# ProPrj___2025-12-10.net
KiCad netlist of a schematic drawn in EasyEDA Pro
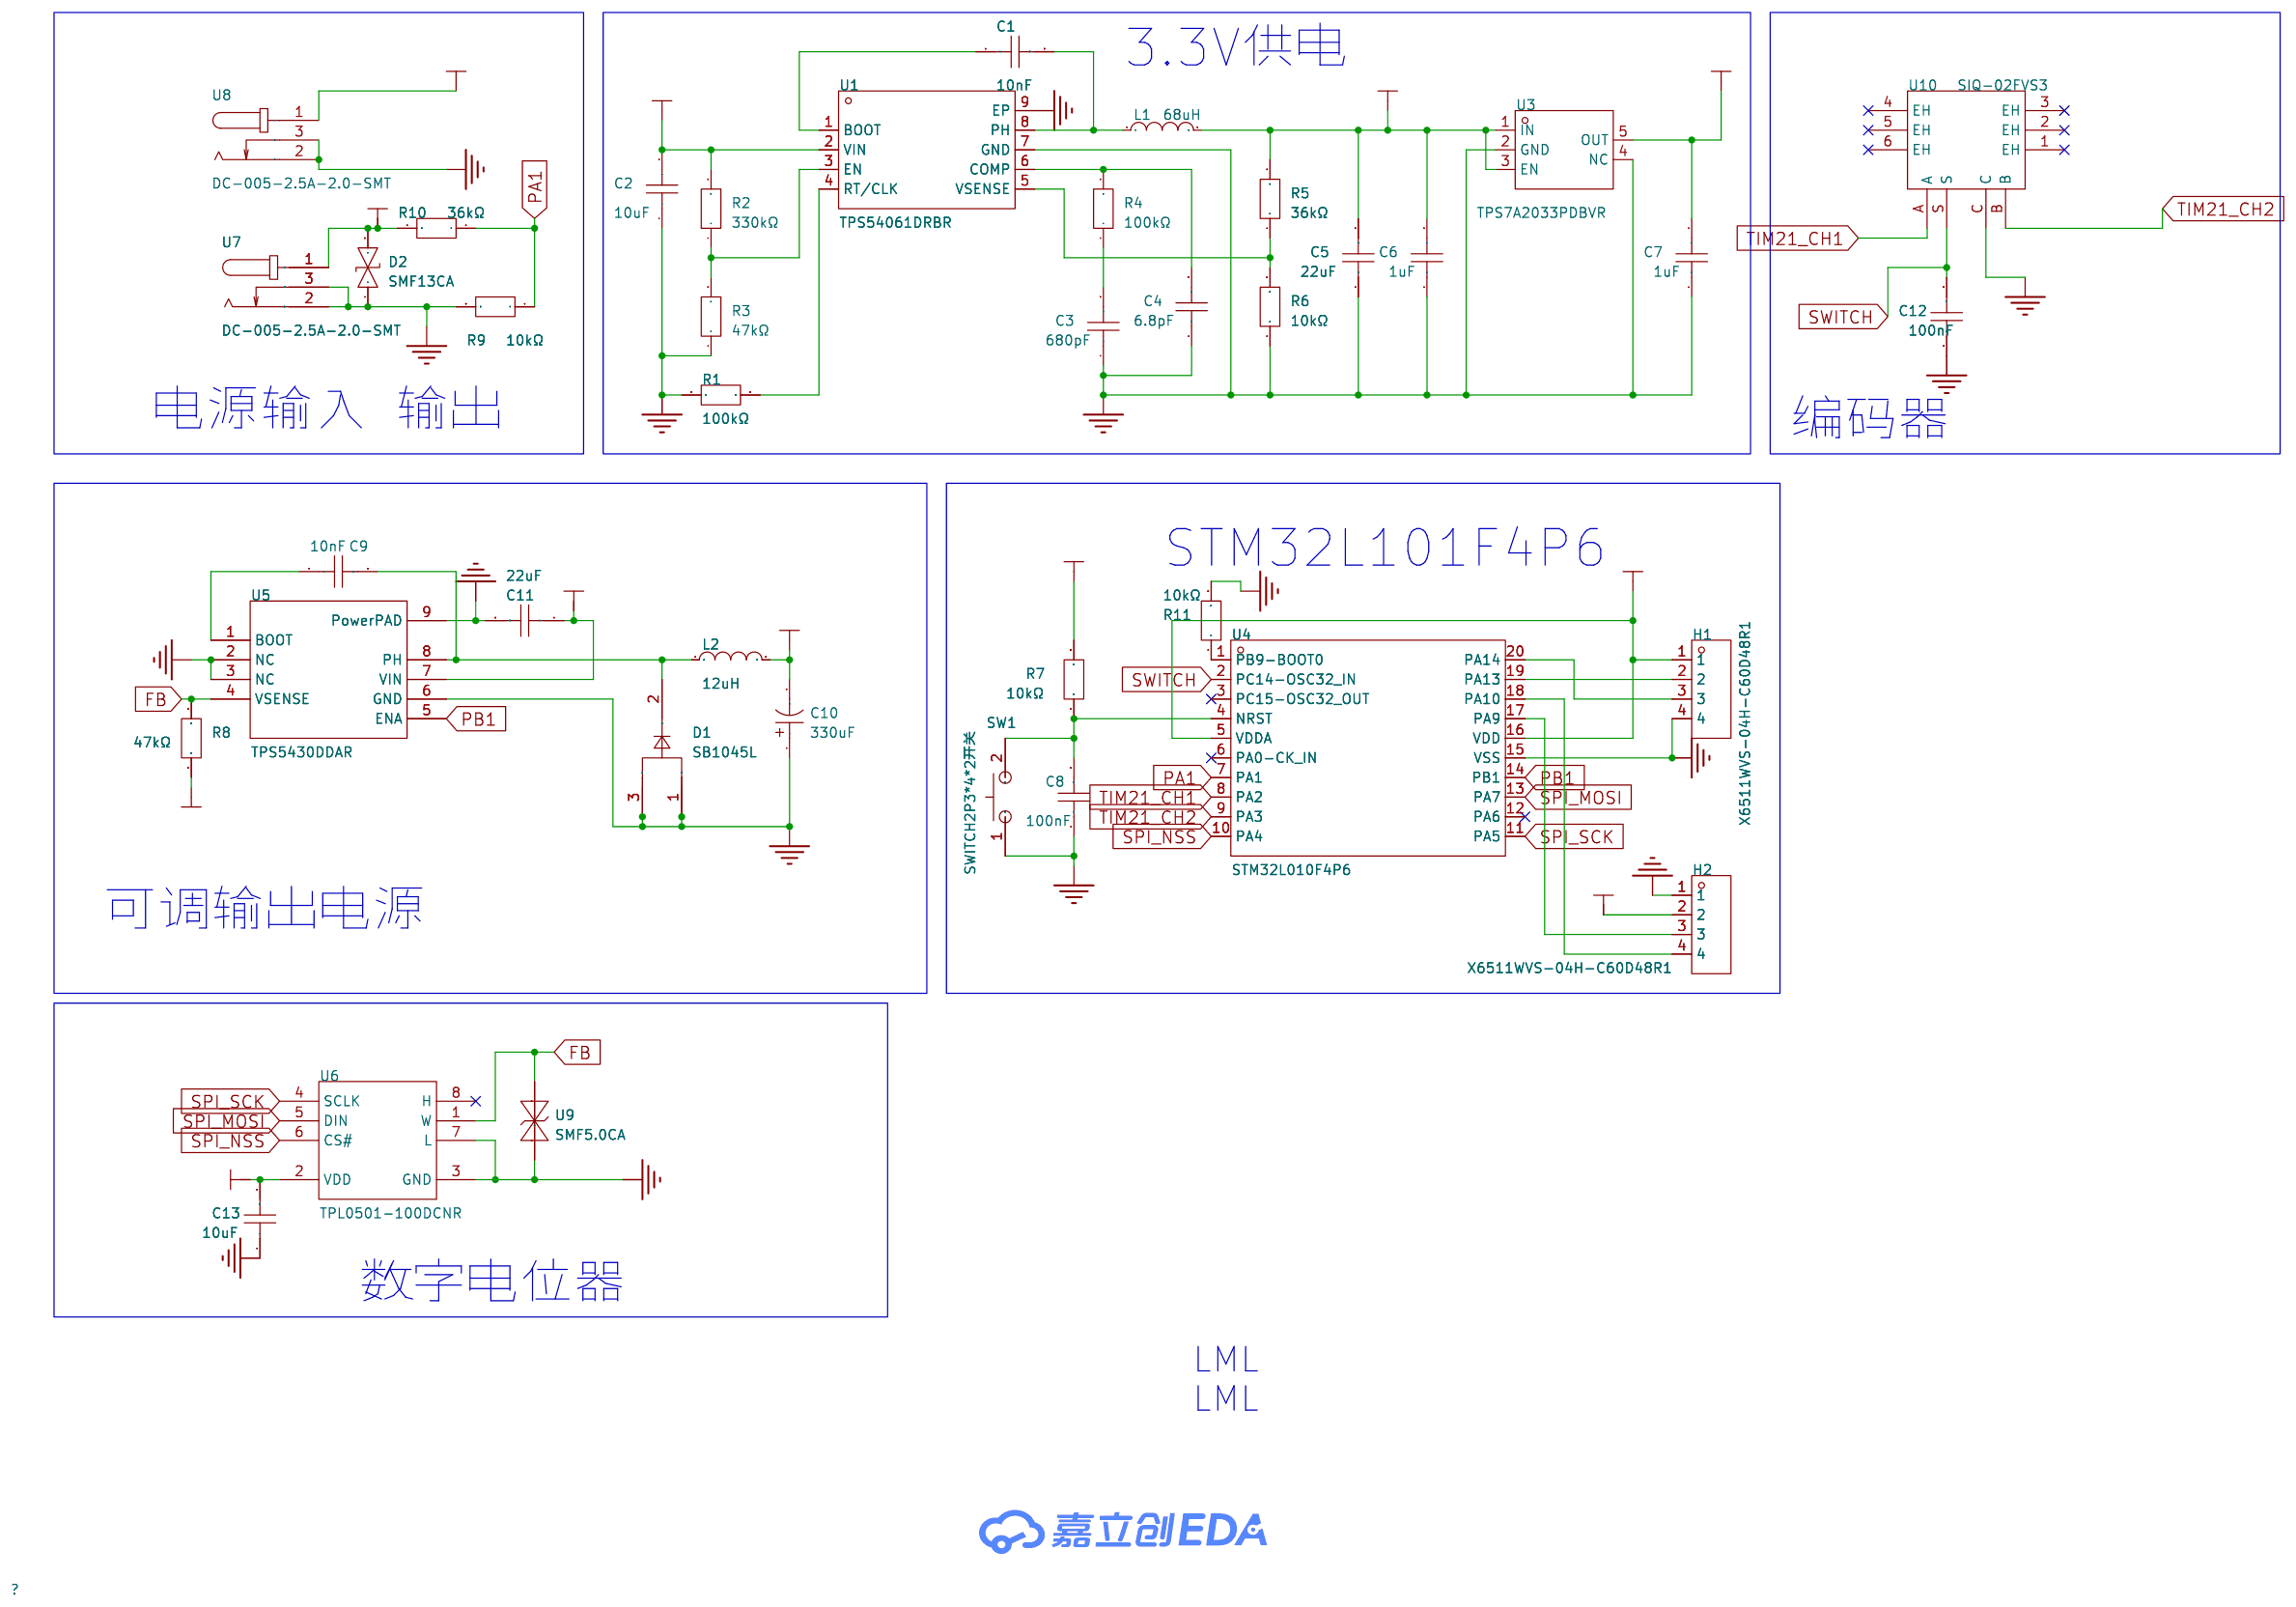
[diagram p0: schematic sheet]

(export (version "E")
  (design (tool "Eeschema 10.0.6"))
  (components
    (comp (ref "C1")
      (value "10nF")
      (footprint "easyedapro:C0603")
      (description "容值:10nF;精度:±10%;额定电压:50V;温度系数:X7R;")
      (fields
        (field (name "Manufacturer Part") "AC0603KPX7R9BB103")
        (field (name "Manufacturer") "YAGEO(国巨)")
      )
      (libsource (lib "easyedapro") (part "AC0603KPX7R9BB103"))
    )
    (comp (ref "C2")
      (value "10uF")
      (footprint "easyedapro:C0603")
      (description "容值:4.7uF;精度:±10%;额定电压:16V;温度系数:X7R;")
      (fields
        (field (name "Manufacturer Part") "GRM188Z71C475KE21J")
        (field (name "Manufacturer") "muRata(村田)")
      )
      (libsource (lib "easyedapro") (part "GRM188Z71C475KE21J"))
    )
    (comp (ref "C3")
      (value "680pF")
      (footprint "easyedapro:C0603")
      (description "容值:4.7uF;精度:±10%;额定电压:16V;温度系数:X7R;")
      (fields
        (field (name "Manufacturer Part") "GRM188Z71C475KE21J")
        (field (name "Manufacturer") "muRata(村田)")
      )
      (libsource (lib "easyedapro") (part "GRM188Z71C475KE21J"))
    )
    (comp (ref "C4")
      (value "6.8pF")
      (footprint "easyedapro:C0603")
      (description "容值:4.7uF;精度:±10%;额定电压:16V;温度系数:X7R;")
      (fields
        (field (name "Manufacturer Part") "GRM188Z71C475KE21J")
        (field (name "Manufacturer") "muRata(村田)")
      )
      (libsource (lib "easyedapro") (part "GRM188Z71C475KE21J"))
    )
    (comp (ref "C5")
      (value "22uF")
      (footprint "easyedapro:C0603")
      (description "容值:4.7uF;精度:±10%;额定电压:16V;温度系数:X7R;")
      (fields
        (field (name "Manufacturer Part") "GRM188Z71C475KE21J")
        (field (name "Manufacturer") "muRata(村田)")
      )
      (libsource (lib "easyedapro") (part "GRM188Z71C475KE21J"))
    )
    (comp (ref "C6")
      (value "1uF")
      (footprint "easyedapro:C0603")
      (description "容值:4.7uF;精度:±10%;额定电压:16V;温度系数:X7R;")
      (fields
        (field (name "Manufacturer Part") "GRM188Z71C475KE21J")
        (field (name "Manufacturer") "muRata(村田)")
      )
      (libsource (lib "easyedapro") (part "GRM188Z71C475KE21J"))
    )
    (comp (ref "C7")
      (value "1uF")
      (footprint "easyedapro:C0603")
      (description "容值:4.7uF;精度:±10%;额定电压:16V;温度系数:X7R;")
      (fields
        (field (name "Manufacturer Part") "GRM188Z71C475KE21J")
        (field (name "Manufacturer") "muRata(村田)")
      )
      (libsource (lib "easyedapro") (part "GRM188Z71C475KE21J"))
    )
    (comp (ref "C8")
      (value "100nF")
      (footprint "easyedapro:C0603")
      (description "容值:10nF;精度:±10%;额定电压:50V;温度系数:X7R;")
      (fields
        (field (name "Manufacturer Part") "AC0603KPX7R9BB103")
        (field (name "Manufacturer") "YAGEO(国巨)")
      )
      (libsource (lib "easyedapro") (part "AC0603KPX7R9BB103"))
    )
    (comp (ref "C9")
      (value "10nF")
      (footprint "easyedapro:C0603")
      (description "容值:10nF;精度:±10%;额定电压:50V;温度系数:X7R;")
      (fields
        (field (name "Manufacturer Part") "AC0603KPX7R9BB103")
        (field (name "Manufacturer") "YAGEO(国巨)")
      )
      (libsource (lib "easyedapro") (part "AC0603KPX7R9BB103"))
    )
    (comp (ref "C10")
      (value "330uF")
      (footprint "easyedapro:CAP-SMD_BD10.0-L10.3-W10.3-SV331M250G12R7R1Z00ZZ")
      (description "容值:330uF;精度:±20%;额定电压:25V;纹波电流:-;等效串联电阻(ESR):-;类型:聚合物;")
      (fields (field (name "Manufacturer Part") "SV331M250G12R7R1Z00ZZ") (field (name "Manufacturer") "创慧电子"))
      (libsource (lib "easyedapro") (part "SV331M250G12R7R1Z00ZZ"))
    )
    (comp (ref "C11")
      (value "22uF")
      (footprint "easyedapro:C0603")
      (description "容值:4.7uF;精度:±10%;额定电压:16V;温度系数:X7R;")
      (fields
        (field (name "Manufacturer Part") "GRM188Z71C475KE21J")
        (field (name "Manufacturer") "muRata(村田)")
      )
      (libsource (lib "easyedapro") (part "GRM188Z71C475KE21J"))
    )
    (comp (ref "C12")
      (value "100nF")
      (footprint "easyedapro:C0603")
      (description "容值:4.7uF;精度:±10%;额定电压:16V;温度系数:X7R;")
      (fields
        (field (name "Manufacturer Part") "GRM188Z71C475KE21J")
        (field (name "Manufacturer") "muRata(村田)")
      )
      (libsource (lib "easyedapro") (part "GRM188Z71C475KE21J"))
    )
    (comp (ref "C13")
      (value "10uF")
      (footprint "easyedapro:C0603")
      (description "容值:4.7uF;精度:±10%;额定电压:16V;温度系数:X7R;")
      (fields
        (field (name "Manufacturer Part") "GRM188Z71C475KE21J")
        (field (name "Manufacturer") "muRata(村田)")
      )
      (libsource (lib "easyedapro") (part "GRM188Z71C475KE21J"))
    )
    (comp (ref "D1")
      (value "SB1045L")
      (footprint "easyedapro:TO-277_3P-L5.4-W4.0-LS6.5-TR")
      (description "二极管配置:独立式;正向压降(Vf):530mV@10A;直流反向耐压(Vr):45V;整流电流:10A;")
      (fields (field (name "Manufacturer") "HXY MOSFET(华轩阳电子)"))
      (libsource (lib "easyedapro") (part "SB1045L_C5199106"))
    )
    (comp (ref "D2")
      (value "SMF13CA")
      (footprint "easyedapro:SOD-123FL_L2.7-W1.8-LS3.8-BI")
      (description "极性:双向;反向截止电压(Vrwm):16V;钳位电压:26V;峰值脉冲电流(Ipp):7.7A@10/1000us;峰值脉冲功率(Ppp):200W@10/1000us;击穿电压:19.7V;")
      (fields (field (name "Manufacturer") "R+O(宏嘉诚)"))
      (libsource (lib "easyedapro") (part "SMF16CA_C2687843"))
    )
    (comp (ref "H1")
      (value "X6511WVS-04H-C60D48R1")
      (footprint "easyedapro:HDR-TH_4P-P2.54-V-F")
      (fields (field (name "Manufacturer") "XKB Connection(中国星坤)"))
      (libsource (lib "easyedapro") (part "2.54-1*4P母"))
    )
    (comp (ref "H2")
      (value "X6511WVS-04H-C60D48R1")
      (footprint "easyedapro:HDR-TH_4P-P2.54-V-F")
      (fields (field (name "Manufacturer") "XKB Connection(中国星坤)"))
      (libsource (lib "easyedapro") (part "2.54-1*4P母"))
    )
    (comp (ref "L1")
      (value "68uH")
      (footprint "easyedapro:IND-SMD_L7.8-W7.0_784787680")
      (description "电感值:68uH;精度:±25%;饱和电流(Isat):1A;")
      (fields (field (name "Manufacturer Part") "784787680") (field (name "Manufacturer") "Wurth(伍尔特)"))
      (libsource (lib "easyedapro") (part "784787680"))
    )
    (comp (ref "L2")
      (value "12uH")
      (footprint "easyedapro:IND-SMD_L12.0-W12.0_744771008")
      (description "电感值:12uH;精度:±20%;额定电流:3.91A;饱和电流(Isat):4.85A;")
      (fields (field (name "Manufacturer Part") "744771112") (field (name "Manufacturer") "Wurth(伍尔特)"))
      (libsource (lib "easyedapro") (part "744771112"))
    )
    (comp (ref "R1")
      (value "100kΩ")
      (footprint "easyedapro:R0603")
      (description "电阻类型:厚膜电阻;阻值:180kΩ;精度:±1%;功率:100mW;工作电压:75V;温度系数:±100ppm/°C;")
      (fields
        (field (name "Manufacturer Part") "GR0603F180KT5G00")
        (field (name "Manufacturer") "GiantOhm(鼎声微电)")
      )
      (libsource (lib "easyedapro") (part "GR0603F180KT5G00"))
    )
    (comp (ref "R2")
      (value "330kΩ")
      (footprint "easyedapro:R0603")
      (description "电阻类型:厚膜电阻;阻值:180kΩ;精度:±1%;功率:100mW;工作电压:75V;温度系数:±100ppm/°C;")
      (fields
        (field (name "Manufacturer Part") "GR0603F180KT5G00")
        (field (name "Manufacturer") "GiantOhm(鼎声微电)")
      )
      (libsource (lib "easyedapro") (part "GR0603F180KT5G00"))
    )
    (comp (ref "R3")
      (value "47kΩ")
      (footprint "easyedapro:R0603")
      (description "电阻类型:厚膜电阻;阻值:180kΩ;精度:±1%;功率:100mW;工作电压:75V;温度系数:±100ppm/°C;")
      (fields
        (field (name "Manufacturer Part") "GR0603F180KT5G00")
        (field (name "Manufacturer") "GiantOhm(鼎声微电)")
      )
      (libsource (lib "easyedapro") (part "GR0603F180KT5G00"))
    )
    (comp (ref "R4")
      (value "100kΩ")
      (footprint "easyedapro:R0603")
      (description "电阻类型:厚膜电阻;阻值:180kΩ;精度:±1%;功率:100mW;工作电压:75V;温度系数:±100ppm/°C;")
      (fields
        (field (name "Manufacturer Part") "GR0603F180KT5G00")
        (field (name "Manufacturer") "GiantOhm(鼎声微电)")
      )
      (libsource (lib "easyedapro") (part "GR0603F180KT5G00"))
    )
    (comp (ref "R5")
      (value "36kΩ")
      (footprint "easyedapro:R0603")
      (description "电阻类型:厚膜电阻;阻值:180kΩ;精度:±1%;功率:100mW;工作电压:75V;温度系数:±100ppm/°C;")
      (fields
        (field (name "Manufacturer Part") "GR0603F180KT5G00")
        (field (name "Manufacturer") "GiantOhm(鼎声微电)")
      )
      (libsource (lib "easyedapro") (part "GR0603F180KT5G00"))
    )
    (comp (ref "R6")
      (value "10kΩ")
      (footprint "easyedapro:R0603")
      (description "电阻类型:厚膜电阻;阻值:180kΩ;精度:±1%;功率:100mW;工作电压:75V;温度系数:±100ppm/°C;")
      (fields
        (field (name "Manufacturer Part") "GR0603F180KT5G00")
        (field (name "Manufacturer") "GiantOhm(鼎声微电)")
      )
      (libsource (lib "easyedapro") (part "GR0603F180KT5G00"))
    )
    (comp (ref "R7")
      (value "10kΩ")
      (footprint "easyedapro:R0603")
      (description "电阻类型:厚膜电阻;阻值:180kΩ;精度:±1%;功率:100mW;工作电压:75V;温度系数:±100ppm/°C;")
      (fields
        (field (name "Manufacturer Part") "GR0603F180KT5G00")
        (field (name "Manufacturer") "GiantOhm(鼎声微电)")
      )
      (libsource (lib "easyedapro") (part "GR0603F180KT5G00"))
    )
    (comp (ref "R8")
      (value "47kΩ")
      (footprint "easyedapro:R0603")
      (description "电阻类型:厚膜电阻;阻值:180kΩ;精度:±1%;功率:100mW;工作电压:75V;温度系数:±100ppm/°C;")
      (fields
        (field (name "Manufacturer Part") "GR0603F180KT5G00")
        (field (name "Manufacturer") "GiantOhm(鼎声微电)")
      )
      (libsource (lib "easyedapro") (part "GR0603F180KT5G00"))
    )
    (comp (ref "R9")
      (value "10kΩ")
      (footprint "easyedapro:R0603")
      (description "电阻类型:厚膜电阻;阻值:180kΩ;精度:±1%;功率:100mW;工作电压:75V;温度系数:±100ppm/°C;")
      (fields
        (field (name "Manufacturer Part") "GR0603F180KT5G00")
        (field (name "Manufacturer") "GiantOhm(鼎声微电)")
      )
      (libsource (lib "easyedapro") (part "GR0603F180KT5G00"))
    )
    (comp (ref "R10")
      (value "36kΩ")
      (footprint "easyedapro:R0603")
      (description "电阻类型:厚膜电阻;阻值:180kΩ;精度:±1%;功率:100mW;工作电压:75V;温度系数:±100ppm/°C;")
      (fields
        (field (name "Manufacturer Part") "GR0603F180KT5G00")
        (field (name "Manufacturer") "GiantOhm(鼎声微电)")
      )
      (libsource (lib "easyedapro") (part "GR0603F180KT5G00"))
    )
    (comp (ref "R11")
      (value "10kΩ")
      (footprint "easyedapro:R0603")
      (description "电阻类型:厚膜电阻;阻值:180kΩ;精度:±1%;功率:100mW;工作电压:75V;温度系数:±100ppm/°C;")
      (fields
        (field (name "Manufacturer Part") "GR0603F180KT5G00")
        (field (name "Manufacturer") "GiantOhm(鼎声微电)")
      )
      (libsource (lib "easyedapro") (part "GR0603F180KT5G00"))
    )
    (comp (ref "SW1")
      (value "SWITCH2P3*4*2开关")
      (footprint "easyedapro:SW-SMD_L3.9-W2.9-P4.15-LS5.0-EH")
      (libsource (lib "easyedapro") (part "SWITCH2P3*4*2开关"))
    )
    (comp (ref "U1")
      (value "TPS54061DRBR")
      (footprint "easyedapro:SON-8_L3.0-W3.0-P0.65-TL-EP")
      (description "功能类型:降压型;输出类型:可调;工作电压:4.7V~60V;输出电压:800mV~58V;输出电流:200mA;")
      (fields (field (name "Manufacturer") "TI(德州仪器)"))
      (libsource (lib "easyedapro") (part "TPS54061DRBR"))
    )
    (comp (ref "U3")
      (value "TPS7A2033PDBVR")
      (footprint "easyedapro:SOT-23-5_L2.9-W1.6-P0.95-LS2.8-BR")
      (description "输出类型:固定;最大输入电压:6V;输出电压:3.3V;输出电流:300mA;输出极性:正极;")
      (fields (field (name "Manufacturer") "TI(德州仪器)"))
      (libsource (lib "easyedapro") (part "TPS7A2033PDBVR"))
    )
    (comp (ref "U4")
      (value "STM32L010F4P6")
      (footprint "easyedapro:TSSOP-20_L6.5-W4.4-P0.65-LS6.4-BL")
      (description "CPU内核:ARM-M系列;CPU最大主频:32MHz;应用领域:-;")
      (fields (field (name "Manufacturer") "ST(意法半导体)"))
      (libsource (lib "easyedapro") (part "STM32L010F4P6"))
    )
    (comp (ref "U5")
      (value "TPS5430DDAR")
      (footprint "easyedapro:ESOP-8_L4.9-W3.9-P1.27-LS6.0-TL-EP")
      (description "功能类型:降压型;工作电压:5.5V~36V;输出电压:1.221V~32.04V;输出电流:3A;输出类型:可调;")
      (fields (field (name "Manufacturer") "TI(德州仪器)"))
      (libsource (lib "easyedapro") (part "TPS5430DDAR"))
    )
    (comp (ref "U6")
      (value "TPL0501-100DCNR")
      (footprint "easyedapro:SOT-23-8_L3.0-W1.7-P0.65-LS2.8-BL")
      (description "电阻值(欧姆):100kΩ;接口类型:SPI;供电电压:2.7V~5.5V;精度:±20%;")
      (fields (field (name "Manufacturer") "TI(德州仪器)"))
      (libsource (lib "easyedapro") (part "TPL0501-100DCNR"))
    )
    (comp (ref "U7")
      (value "DC-005-2.5A-2.0-SMT")
      (footprint "easyedapro:DC-IN-TH_XKB_DC-005-2.5A-2.5-SMT")
      (description "连接器类型:DC电源插座;安装方式:卧贴;触点内径:2mm;触点外径:6.5mm;额定电流:2.5A;额定电压:24V;工作温度:-;")
      (fields (field (name "Manufacturer") "XKB Connection(中国星坤)"))
      (libsource (lib "easyedapro") (part "DC-005-2.5A-2.0-SMT"))
    )
    (comp (ref "U8")
      (value "DC-005-2.5A-2.0-SMT")
      (footprint "easyedapro:DC-IN-TH_XKB_DC-005-2.5A-2.5-SMT")
      (description "连接器类型:DC电源插座;安装方式:卧贴;触点内径:2mm;触点外径:6.5mm;额定电流:2.5A;额定电压:24V;工作温度:-;")
      (fields (field (name "Manufacturer") "XKB Connection(中国星坤)"))
      (libsource (lib "easyedapro") (part "DC-005-2.5A-2.0-SMT"))
    )
    (comp (ref "U9")
      (value "SMF5.0CA")
      (footprint "easyedapro:SOD-123FL_L2.8-W1.8-LS3.7-BI")
      (description "反向截止电压(Vrwm):5V;最大钳位电压:9.2V;峰值脉冲电流(Ipp):21.7A;峰值脉冲功率(Ppp):200W;击穿电压:6.4V;")
      (fields (field (name "Manufacturer") "KUU"))
      (libsource (lib "easyedapro") (part "SMF5.0CA_C2985633"))
    )
    (comp (ref "U10")
      (value "SIQ-02FVS3")
      (footprint "easyedapro:SW-SMD_SIQ-02FVS3_1")
      (fields (field (name "Manufacturer") "MITSUMI(美上美)"))
      (libsource (lib "easyedapro") (part "SIQ-02FVS3"))
    )
  )
  (nets
    (net (code "1") (name "+3.3V") (class "Default")
      (node (ref "C13") (pin "2") (pinfunction "2_2") (pintype "unspecified"))
      (node (ref "C7") (pin "2") (pinfunction "2_2") (pintype "unspecified"))
      (node (ref "H1") (pin "1") (pinfunction "1_1") (pintype "unspecified"))
      (node (ref "H2") (pin "2") (pinfunction "2_2") (pintype "unspecified"))
      (node (ref "R7") (pin "2") (pinfunction "2_2") (pintype "unspecified"))
      (node (ref "U3") (pin "5") (pinfunction "OUT_5") (pintype "unspecified"))
      (node (ref "U4") (pin "16") (pinfunction "VDD_16") (pintype "unspecified"))
      (node (ref "U4") (pin "5") (pinfunction "VDDA_5") (pintype "unspecified"))
      (node (ref "U6") (pin "2") (pinfunction "VDD_2") (pintype "unspecified"))
    )
    (net (code "2") (name "+3.6V") (class "Default")
      (node (ref "C5") (pin "2") (pinfunction "2_2") (pintype "unspecified"))
      (node (ref "C6") (pin "2") (pinfunction "2_2") (pintype "unspecified"))
      (node (ref "L1") (pin "2") (pinfunction "2_2") (pintype "unspecified"))
      (node (ref "R5") (pin "2") (pinfunction "2_2") (pintype "unspecified"))
      (node (ref "U3") (pin "1") (pinfunction "IN_1") (pintype "unspecified"))
      (node (ref "U3") (pin "3") (pinfunction "EN_3") (pintype "unspecified"))
    )
    (net (code "3") (name "+8V") (class "Default")
      (node (ref "C10") (pin "2") (pinfunction "2_2") (pintype "input"))
      (node (ref "D2") (pin "2") (pinfunction "A_2") (pintype "unspecified"))
      (node (ref "L2") (pin "2") (pinfunction "2_2") (pintype "unspecified"))
      (node (ref "R10") (pin "2") (pinfunction "2_2") (pintype "unspecified"))
      (node (ref "R8") (pin "1") (pinfunction "1_1") (pintype "unspecified"))
      (node (ref "U7") (pin "1") (pinfunction "1_1") (pintype "unspecified"))
    )
    (net (code "4") (name "+12V") (class "Default")
      (node (ref "C11") (pin "1") (pinfunction "1_1") (pintype "unspecified"))
      (node (ref "C2") (pin "2") (pinfunction "2_2") (pintype "unspecified"))
      (node (ref "R2") (pin "2") (pinfunction "2_2") (pintype "unspecified"))
      (node (ref "U1") (pin "2") (pinfunction "VIN_2") (pintype "unspecified"))
      (node (ref "U5") (pin "7") (pinfunction "VIN_7") (pintype "unspecified"))
      (node (ref "U8") (pin "1") (pinfunction "1_1") (pintype "unspecified"))
    )
    (net (code "5") (name "FB") (class "Default")
      (node (ref "R8") (pin "2") (pinfunction "2_2") (pintype "unspecified"))
      (node (ref "U5") (pin "4") (pinfunction "VSENSE_4") (pintype "unspecified"))
      (node (ref "U6") (pin "1") (pinfunction "W_1") (pintype "unspecified"))
      (node (ref "U9") (pin "2") (pinfunction "2_2") (pintype "unspecified"))
    )
    (net (code "6") (name "GND") (class "Default")
      (node (ref "C10") (pin "1") (pinfunction "1_1") (pintype "input"))
      (node (ref "C11") (pin "2") (pinfunction "2_2") (pintype "unspecified"))
      (node (ref "C12") (pin "1") (pinfunction "1_1") (pintype "unspecified"))
      (node (ref "C13") (pin "1") (pinfunction "1_1") (pintype "unspecified"))
      (node (ref "C2") (pin "1") (pinfunction "1_1") (pintype "unspecified"))
      (node (ref "C3") (pin "1") (pinfunction "1_1") (pintype "unspecified"))
      (node (ref "C4") (pin "1") (pinfunction "1_1") (pintype "unspecified"))
      (node (ref "C5") (pin "1") (pinfunction "1_1") (pintype "unspecified"))
      (node (ref "C6") (pin "1") (pinfunction "1_1") (pintype "unspecified"))
      (node (ref "C7") (pin "1") (pinfunction "1_1") (pintype "unspecified"))
      (node (ref "C8") (pin "1") (pinfunction "1_1") (pintype "unspecified"))
      (node (ref "D1") (pin "1") (pinfunction "A_1") (pintype "unspecified"))
      (node (ref "D1") (pin "3") (pinfunction "A_3") (pintype "unspecified"))
      (node (ref "D2") (pin "1") (pinfunction "K_1") (pintype "unspecified"))
      (node (ref "H1") (pin "4") (pinfunction "4_4") (pintype "unspecified"))
      (node (ref "H2") (pin "1") (pinfunction "1_1") (pintype "unspecified"))
      (node (ref "R1") (pin "1") (pinfunction "1_1") (pintype "unspecified"))
      (node (ref "R11") (pin "2") (pinfunction "2_2") (pintype "unspecified"))
      (node (ref "R3") (pin "1") (pinfunction "1_1") (pintype "unspecified"))
      (node (ref "R6") (pin "1") (pinfunction "1_1") (pintype "unspecified"))
      (node (ref "R9") (pin "2") (pinfunction "2_2") (pintype "unspecified"))
      (node (ref "SW1") (pin "1") (pinfunction "1_1") (pintype "unspecified"))
      (node (ref "U1") (pin "7") (pinfunction "GND_7") (pintype "unspecified"))
      (node (ref "U1") (pin "9") (pinfunction "EP_9") (pintype "unspecified"))
      (node (ref "U10") (pin "C") (pinfunction "C_C") (pintype "unspecified"))
      (node (ref "U3") (pin "2") (pinfunction "GND_2") (pintype "unspecified"))
      (node (ref "U3") (pin "4") (pinfunction "NC_4") (pintype "unspecified"))
      (node (ref "U4") (pin "15") (pinfunction "VSS_15") (pintype "unspecified"))
      (node (ref "U5") (pin "2") (pinfunction "NC_2") (pintype "unspecified"))
      (node (ref "U5") (pin "3") (pinfunction "NC_3") (pintype "unspecified"))
      (node (ref "U5") (pin "6") (pinfunction "GND_6") (pintype "unspecified"))
      (node (ref "U5") (pin "9") (pinfunction "PowerPAD_9") (pintype "unspecified"))
      (node (ref "U6") (pin "3") (pinfunction "GND_3") (pintype "unspecified"))
      (node (ref "U6") (pin "7") (pinfunction "L_7") (pintype "unspecified"))
      (node (ref "U7") (pin "2") (pinfunction "2_2") (pintype "unspecified"))
      (node (ref "U7") (pin "3") (pinfunction "3_3") (pintype "unspecified"))
      (node (ref "U8") (pin "2") (pinfunction "2_2") (pintype "unspecified"))
      (node (ref "U8") (pin "3") (pinfunction "3_3") (pintype "unspecified"))
      (node (ref "U9") (pin "1") (pinfunction "1_1") (pintype "unspecified"))
    )
    (net (code "7") (name "Net-(C3-Pad2)") (class "Default")
      (node (ref "C3") (pin "2") (pinfunction "2_2") (pintype "unspecified"))
      (node (ref "R4") (pin "1") (pinfunction "1_1") (pintype "unspecified"))
    )
    (net (code "8") (name "Net-(D1-C)") (class "Default")
      (node (ref "C9") (pin "2") (pinfunction "2_2") (pintype "unspecified"))
      (node (ref "D1") (pin "2") (pinfunction "C_2") (pintype "unspecified"))
      (node (ref "L2") (pin "1") (pinfunction "1_1") (pintype "unspecified"))
      (node (ref "U5") (pin "8") (pinfunction "PH_8") (pintype "unspecified"))
    )
    (net (code "9") (name "Net-(U1-BOOT)") (class "Default")
      (node (ref "C1") (pin "1") (pinfunction "1_1") (pintype "unspecified"))
      (node (ref "U1") (pin "1") (pinfunction "BOOT_1") (pintype "unspecified"))
    )
    (net (code "10") (name "Net-(U1-COMP)") (class "Default")
      (node (ref "C4") (pin "2") (pinfunction "2_2") (pintype "unspecified"))
      (node (ref "R4") (pin "2") (pinfunction "2_2") (pintype "unspecified"))
      (node (ref "U1") (pin "6") (pinfunction "COMP_6") (pintype "unspecified"))
    )
    (net (code "11") (name "Net-(U1-EN)") (class "Default")
      (node (ref "R2") (pin "1") (pinfunction "1_1") (pintype "unspecified"))
      (node (ref "R3") (pin "2") (pinfunction "2_2") (pintype "unspecified"))
      (node (ref "U1") (pin "3") (pinfunction "EN_3") (pintype "unspecified"))
    )
    (net (code "12") (name "Net-(U1-PH)") (class "Default")
      (node (ref "C1") (pin "2") (pinfunction "2_2") (pintype "unspecified"))
      (node (ref "L1") (pin "1") (pinfunction "1_1") (pintype "unspecified"))
      (node (ref "U1") (pin "8") (pinfunction "PH_8") (pintype "unspecified"))
    )
    (net (code "13") (name "Net-(U1-RT{slash}CLK)") (class "Default")
      (node (ref "R1") (pin "2") (pinfunction "2_2") (pintype "unspecified"))
      (node (ref "U1") (pin "4") (pinfunction "RT/CLK_4") (pintype "unspecified"))
    )
    (net (code "14") (name "Net-(U1-VSENSE)") (class "Default")
      (node (ref "R5") (pin "1") (pinfunction "1_1") (pintype "unspecified"))
      (node (ref "R6") (pin "2") (pinfunction "2_2") (pintype "unspecified"))
      (node (ref "U1") (pin "5") (pinfunction "VSENSE_5") (pintype "unspecified"))
    )
    (net (code "15") (name "Net-(U4-NRST)") (class "Default")
      (node (ref "C8") (pin "2") (pinfunction "2_2") (pintype "unspecified"))
      (node (ref "R7") (pin "1") (pinfunction "1_1") (pintype "unspecified"))
      (node (ref "SW1") (pin "2") (pinfunction "2_2") (pintype "unspecified"))
      (node (ref "U4") (pin "4") (pinfunction "NRST_4") (pintype "unspecified"))
    )
    (net (code "16") (name "Net-(U4-PA9)") (class "Default")
      (node (ref "H2") (pin "3") (pinfunction "3_3") (pintype "unspecified"))
      (node (ref "U4") (pin "17") (pinfunction "PA9_17") (pintype "unspecified"))
    )
    (net (code "17") (name "Net-(U4-PA10)") (class "Default")
      (node (ref "H2") (pin "4") (pinfunction "4_4") (pintype "unspecified"))
      (node (ref "U4") (pin "18") (pinfunction "PA10_18") (pintype "unspecified"))
    )
    (net (code "18") (name "Net-(U4-PA13)") (class "Default")
      (node (ref "H1") (pin "2") (pinfunction "2_2") (pintype "unspecified"))
      (node (ref "U4") (pin "19") (pinfunction "PA13_19") (pintype "unspecified"))
    )
    (net (code "19") (name "Net-(U4-PA14)") (class "Default")
      (node (ref "H1") (pin "3") (pinfunction "3_3") (pintype "unspecified"))
      (node (ref "U4") (pin "20") (pinfunction "PA14_20") (pintype "unspecified"))
    )
    (net (code "20") (name "Net-(U4-PB9-BOOT0)") (class "Default")
      (node (ref "R11") (pin "1") (pinfunction "1_1") (pintype "unspecified"))
      (node (ref "U4") (pin "1") (pinfunction "PB9-BOOT0_1") (pintype "unspecified"))
    )
    (net (code "21") (name "Net-(U5-BOOT)") (class "Default")
      (node (ref "C9") (pin "1") (pinfunction "1_1") (pintype "unspecified"))
      (node (ref "U5") (pin "1") (pinfunction "BOOT_1") (pintype "unspecified"))
    )
    (net (code "22") (name "PA1") (class "Default")
      (node (ref "R10") (pin "1") (pinfunction "1_1") (pintype "unspecified"))
      (node (ref "R9") (pin "1") (pinfunction "1_1") (pintype "unspecified"))
      (node (ref "U4") (pin "7") (pinfunction "PA1_7") (pintype "unspecified"))
    )
    (net (code "23") (name "PB1") (class "Default")
      (node (ref "U4") (pin "14") (pinfunction "PB1_14") (pintype "unspecified"))
      (node (ref "U5") (pin "5") (pinfunction "ENA_5") (pintype "unspecified"))
    )
    (net (code "24") (name "SPI_MOSI") (class "Default")
      (node (ref "U4") (pin "13") (pinfunction "PA7_13") (pintype "unspecified"))
      (node (ref "U6") (pin "5") (pinfunction "DIN_5") (pintype "unspecified"))
    )
    (net (code "25") (name "SPI_NSS") (class "Default")
      (node (ref "U4") (pin "10") (pinfunction "PA4_10") (pintype "unspecified"))
      (node (ref "U6") (pin "6") (pinfunction "CS#_6") (pintype "unspecified"))
    )
    (net (code "26") (name "SPI_SCK") (class "Default")
      (node (ref "U4") (pin "11") (pinfunction "PA5_11") (pintype "unspecified"))
      (node (ref "U6") (pin "4") (pinfunction "SCLK_4") (pintype "unspecified"))
    )
    (net (code "27") (name "SWITCH") (class "Default")
      (node (ref "C12") (pin "2") (pinfunction "2_2") (pintype "unspecified"))
      (node (ref "U10") (pin "S") (pinfunction "S_S") (pintype "unspecified"))
      (node (ref "U4") (pin "2") (pinfunction "PC14-OSC32_IN_2") (pintype "unspecified"))
    )
    (net (code "28") (name "TIM21_CH1") (class "Default")
      (node (ref "U10") (pin "A") (pinfunction "A_A") (pintype "unspecified"))
      (node (ref "U4") (pin "8") (pinfunction "PA2_8") (pintype "unspecified"))
    )
    (net (code "29") (name "TIM21_CH2") (class "Default")
      (node (ref "U10") (pin "B") (pinfunction "B_B") (pintype "unspecified"))
      (node (ref "U4") (pin "9") (pinfunction "PA3_9") (pintype "unspecified"))
    )
    (net (code "30") (name "unconnected-(U4-PA0-CK_IN-Pad6)") (class "Default")
      (node (ref "U4") (pin "6") (pinfunction "PA0-CK_IN_6") (pintype "unspecified+no_connect"))
    )
    (net (code "31") (name "unconnected-(U4-PA6-Pad12)") (class "Default")
      (node (ref "U4") (pin "12") (pinfunction "PA6_12") (pintype "unspecified+no_connect"))
    )
    (net (code "32") (name "unconnected-(U4-PC15-OSC32_OUT-Pad3)") (class "Default")
      (node (ref "U4") (pin "3") (pinfunction "PC15-OSC32_OUT_3") (pintype "unspecified+no_connect"))
    )
    (net (code "33") (name "unconnected-(U6-H-Pad8)") (class "Default")
      (node (ref "U6") (pin "8") (pinfunction "H_8") (pintype "unspecified+no_connect"))
    )
    (net (code "34") (name "unconnected-(U10-EH-Pad1)") (class "Default")
      (node (ref "U10") (pin "1") (pinfunction "EH_1") (pintype "unspecified+no_connect"))
    )
    (net (code "35") (name "unconnected-(U10-EH-Pad2)") (class "Default")
      (node (ref "U10") (pin "2") (pinfunction "EH_2") (pintype "unspecified+no_connect"))
    )
    (net (code "36") (name "unconnected-(U10-EH-Pad3)") (class "Default")
      (node (ref "U10") (pin "3") (pinfunction "EH_3") (pintype "unspecified+no_connect"))
    )
    (net (code "37") (name "unconnected-(U10-EH-Pad4)") (class "Default")
      (node (ref "U10") (pin "4") (pinfunction "EH_4") (pintype "unspecified+no_connect"))
    )
    (net (code "38") (name "unconnected-(U10-EH-Pad5)") (class "Default")
      (node (ref "U10") (pin "5") (pinfunction "EH_5") (pintype "unspecified+no_connect"))
    )
    (net (code "39") (name "unconnected-(U10-EH-Pad6)") (class "Default")
      (node (ref "U10") (pin "6") (pinfunction "EH_6") (pintype "unspecified+no_connect"))
    )
  )
)
